# brain_v01.net
KiCad netlist of a schematic drawn in EAGLE
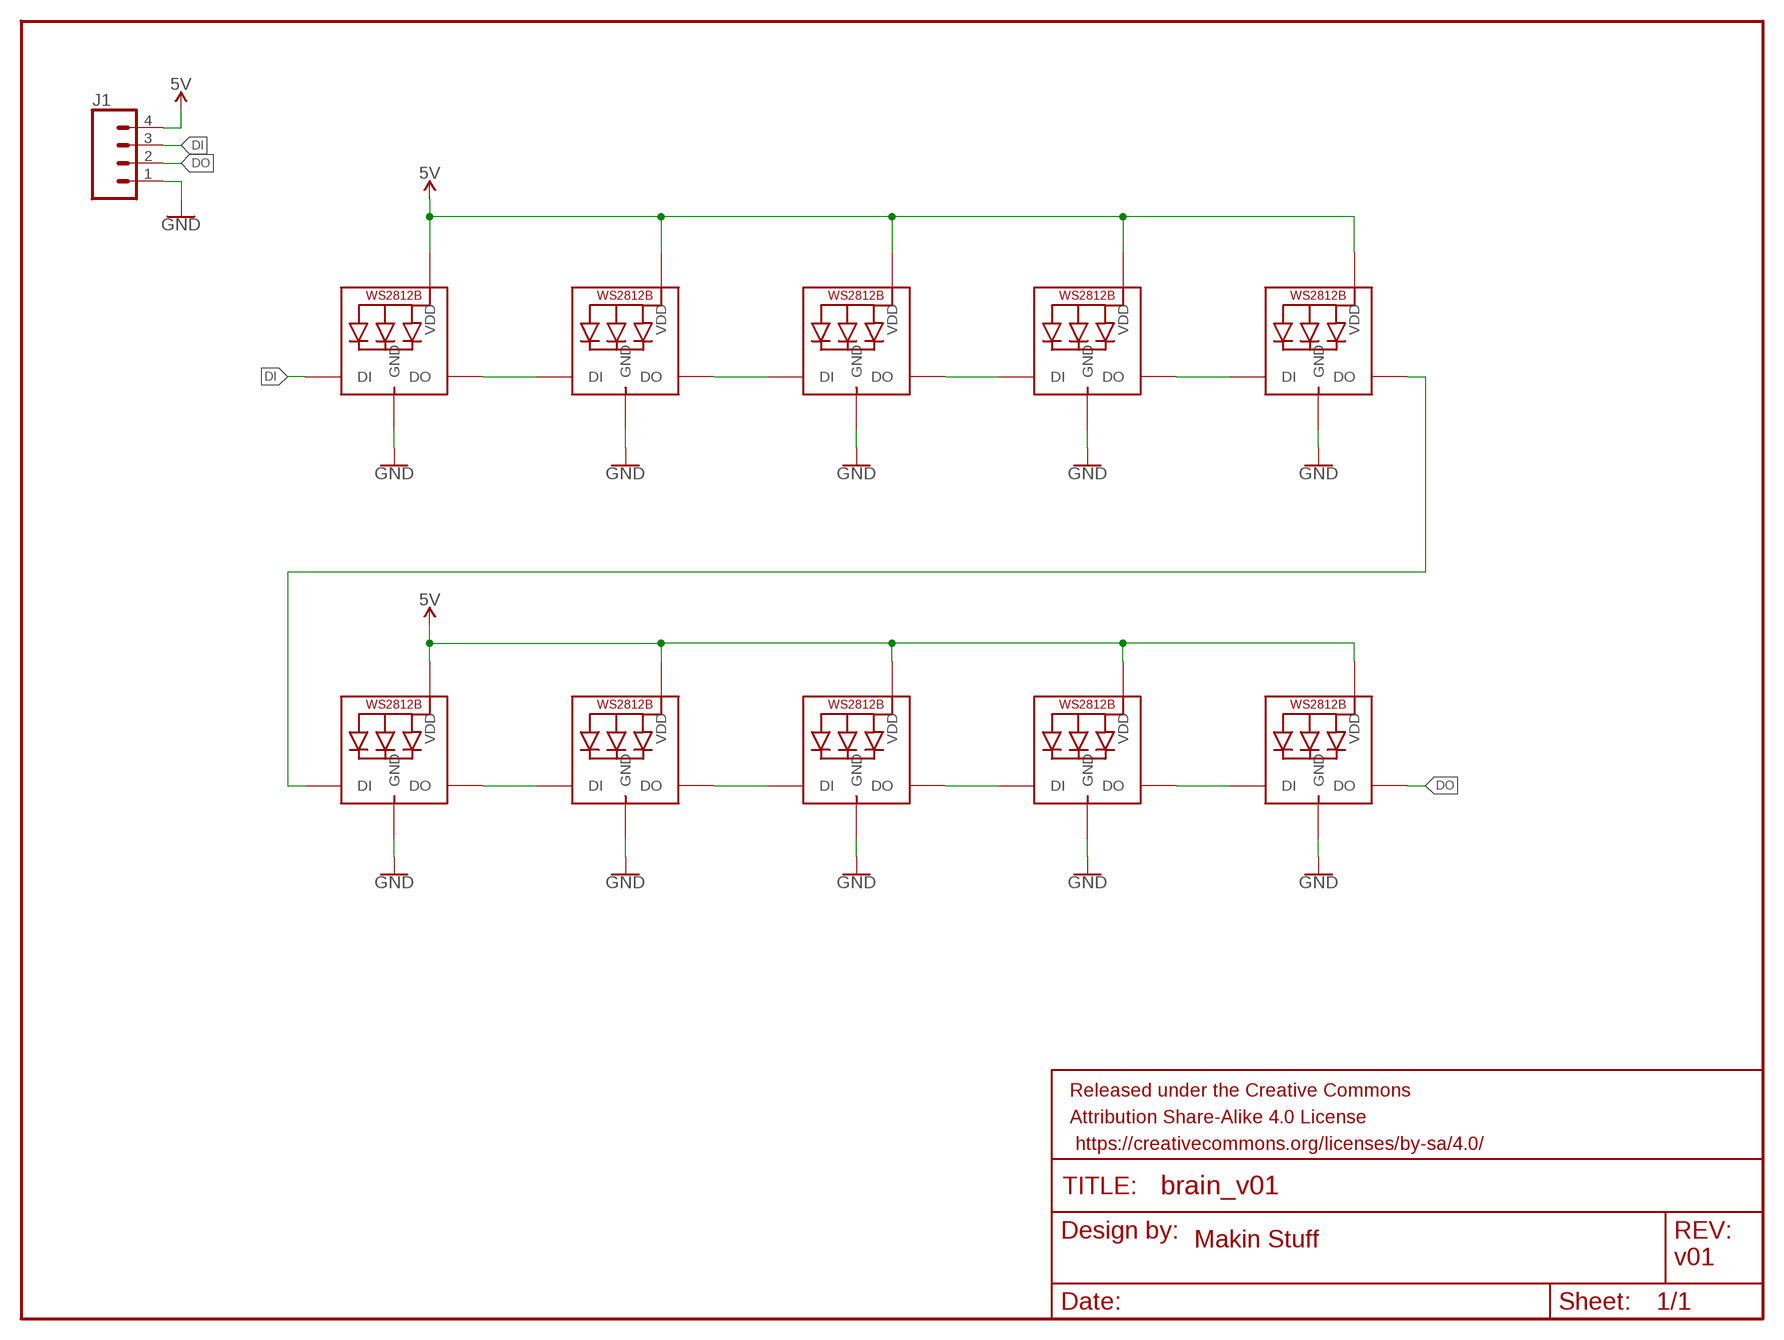
[diagram p0: schematic, sheet 1]

(export (version "E")
  (design (tool "Eeschema 10.0.6"))
  (components
    (comp (ref "FRAME1")
      (value "FRAME-LETTER")
      (footprint "eagle-import:CREATIVE_COMMONS")
      (libsource (lib "eagle-import") (part "FRAME-LETTER"))
    )
    (comp (ref "J1")
      (value "CONN_04PTH")
      (footprint "eagle-import:1X04")
      (libsource (lib "eagle-import") (part "CONN_04PTH"))
    )
    (comp (ref "LED1")
      (value "WS2812B3535")
      (footprint "eagle-import:LED3535")
      (libsource (lib "eagle-import") (part "WS2812B3535"))
    )
    (comp (ref "LED2")
      (value "WS2812B3535")
      (footprint "eagle-import:LED3535")
      (libsource (lib "eagle-import") (part "WS2812B3535"))
    )
    (comp (ref "LED3")
      (value "WS2812B3535")
      (footprint "eagle-import:LED3535")
      (libsource (lib "eagle-import") (part "WS2812B3535"))
    )
    (comp (ref "LED4")
      (value "WS2812B3535")
      (footprint "eagle-import:LED3535")
      (libsource (lib "eagle-import") (part "WS2812B3535"))
    )
    (comp (ref "LED5")
      (value "WS2812B3535")
      (footprint "eagle-import:LED3535")
      (libsource (lib "eagle-import") (part "WS2812B3535"))
    )
    (comp (ref "LED6")
      (value "WS2812B3535")
      (footprint "eagle-import:LED3535")
      (libsource (lib "eagle-import") (part "WS2812B3535"))
    )
    (comp (ref "LED7")
      (value "WS2812B3535")
      (footprint "eagle-import:LED3535")
      (libsource (lib "eagle-import") (part "WS2812B3535"))
    )
    (comp (ref "LED8")
      (value "WS2812B3535")
      (footprint "eagle-import:LED3535")
      (libsource (lib "eagle-import") (part "WS2812B3535"))
    )
    (comp (ref "LED9")
      (value "WS2812B3535")
      (footprint "eagle-import:LED3535")
      (libsource (lib "eagle-import") (part "WS2812B3535"))
    )
    (comp (ref "LED10")
      (value "WS2812B3535")
      (footprint "eagle-import:LED3535")
      (libsource (lib "eagle-import") (part "WS2812B3535"))
    )
  )
  (nets
    (net (code "1") (name "5V") (class "Default")
      (node (ref "J1") (pin "4") (pinfunction "4_4") (pintype "passive"))
      (node (ref "LED1") (pin "2") (pinfunction "VDD_2") (pintype "power_in"))
      (node (ref "LED10") (pin "2") (pinfunction "VDD_2") (pintype "power_in"))
      (node (ref "LED2") (pin "2") (pinfunction "VDD_2") (pintype "power_in"))
      (node (ref "LED3") (pin "2") (pinfunction "VDD_2") (pintype "power_in"))
      (node (ref "LED4") (pin "2") (pinfunction "VDD_2") (pintype "power_in"))
      (node (ref "LED5") (pin "2") (pinfunction "VDD_2") (pintype "power_in"))
      (node (ref "LED6") (pin "2") (pinfunction "VDD_2") (pintype "power_in"))
      (node (ref "LED7") (pin "2") (pinfunction "VDD_2") (pintype "power_in"))
      (node (ref "LED8") (pin "2") (pinfunction "VDD_2") (pintype "power_in"))
      (node (ref "LED9") (pin "2") (pinfunction "VDD_2") (pintype "power_in"))
    )
    (net (code "2") (name "DI") (class "Default")
      (node (ref "J1") (pin "3") (pinfunction "3_3") (pintype "passive"))
      (node (ref "LED1") (pin "1") (pinfunction "DI_1") (pintype "input"))
    )
    (net (code "3") (name "DO") (class "Default")
      (node (ref "J1") (pin "2") (pinfunction "2_2") (pintype "passive"))
      (node (ref "LED10") (pin "3") (pinfunction "DO_3") (pintype "output"))
    )
    (net (code "4") (name "GND") (class "Default")
      (node (ref "J1") (pin "1") (pinfunction "1_1") (pintype "passive"))
      (node (ref "LED1") (pin "4") (pinfunction "GND_4") (pintype "power_in"))
      (node (ref "LED10") (pin "4") (pinfunction "GND_4") (pintype "power_in"))
      (node (ref "LED2") (pin "4") (pinfunction "GND_4") (pintype "power_in"))
      (node (ref "LED3") (pin "4") (pinfunction "GND_4") (pintype "power_in"))
      (node (ref "LED4") (pin "4") (pinfunction "GND_4") (pintype "power_in"))
      (node (ref "LED5") (pin "4") (pinfunction "GND_4") (pintype "power_in"))
      (node (ref "LED6") (pin "4") (pinfunction "GND_4") (pintype "power_in"))
      (node (ref "LED7") (pin "4") (pinfunction "GND_4") (pintype "power_in"))
      (node (ref "LED8") (pin "4") (pinfunction "GND_4") (pintype "power_in"))
      (node (ref "LED9") (pin "4") (pinfunction "GND_4") (pintype "power_in"))
    )
    (net (code "5") (name "Net-(LED1-DO)") (class "Default")
      (node (ref "LED1") (pin "3") (pinfunction "DO_3") (pintype "output"))
      (node (ref "LED2") (pin "1") (pinfunction "DI_1") (pintype "input"))
    )
    (net (code "6") (name "Net-(LED2-DO)") (class "Default")
      (node (ref "LED2") (pin "3") (pinfunction "DO_3") (pintype "output"))
      (node (ref "LED3") (pin "1") (pinfunction "DI_1") (pintype "input"))
    )
    (net (code "7") (name "Net-(LED3-DO)") (class "Default")
      (node (ref "LED3") (pin "3") (pinfunction "DO_3") (pintype "output"))
      (node (ref "LED4") (pin "1") (pinfunction "DI_1") (pintype "input"))
    )
    (net (code "8") (name "Net-(LED4-DO)") (class "Default")
      (node (ref "LED4") (pin "3") (pinfunction "DO_3") (pintype "output"))
      (node (ref "LED5") (pin "1") (pinfunction "DI_1") (pintype "input"))
    )
    (net (code "9") (name "Net-(LED5-DO)") (class "Default")
      (node (ref "LED5") (pin "3") (pinfunction "DO_3") (pintype "output"))
      (node (ref "LED6") (pin "1") (pinfunction "DI_1") (pintype "input"))
    )
    (net (code "10") (name "Net-(LED6-DO)") (class "Default")
      (node (ref "LED6") (pin "3") (pinfunction "DO_3") (pintype "output"))
      (node (ref "LED7") (pin "1") (pinfunction "DI_1") (pintype "input"))
    )
    (net (code "11") (name "Net-(LED7-DO)") (class "Default")
      (node (ref "LED7") (pin "3") (pinfunction "DO_3") (pintype "output"))
      (node (ref "LED8") (pin "1") (pinfunction "DI_1") (pintype "input"))
    )
    (net (code "12") (name "Net-(LED8-DO)") (class "Default")
      (node (ref "LED8") (pin "3") (pinfunction "DO_3") (pintype "output"))
      (node (ref "LED9") (pin "1") (pinfunction "DI_1") (pintype "input"))
    )
    (net (code "13") (name "Net-(LED10-DI)") (class "Default")
      (node (ref "LED10") (pin "1") (pinfunction "DI_1") (pintype "input"))
      (node (ref "LED9") (pin "3") (pinfunction "DO_3") (pintype "output"))
    )
  )
)
